# STM_Central_Circuit.net
KiCad netlist of a schematic drawn in EAGLE
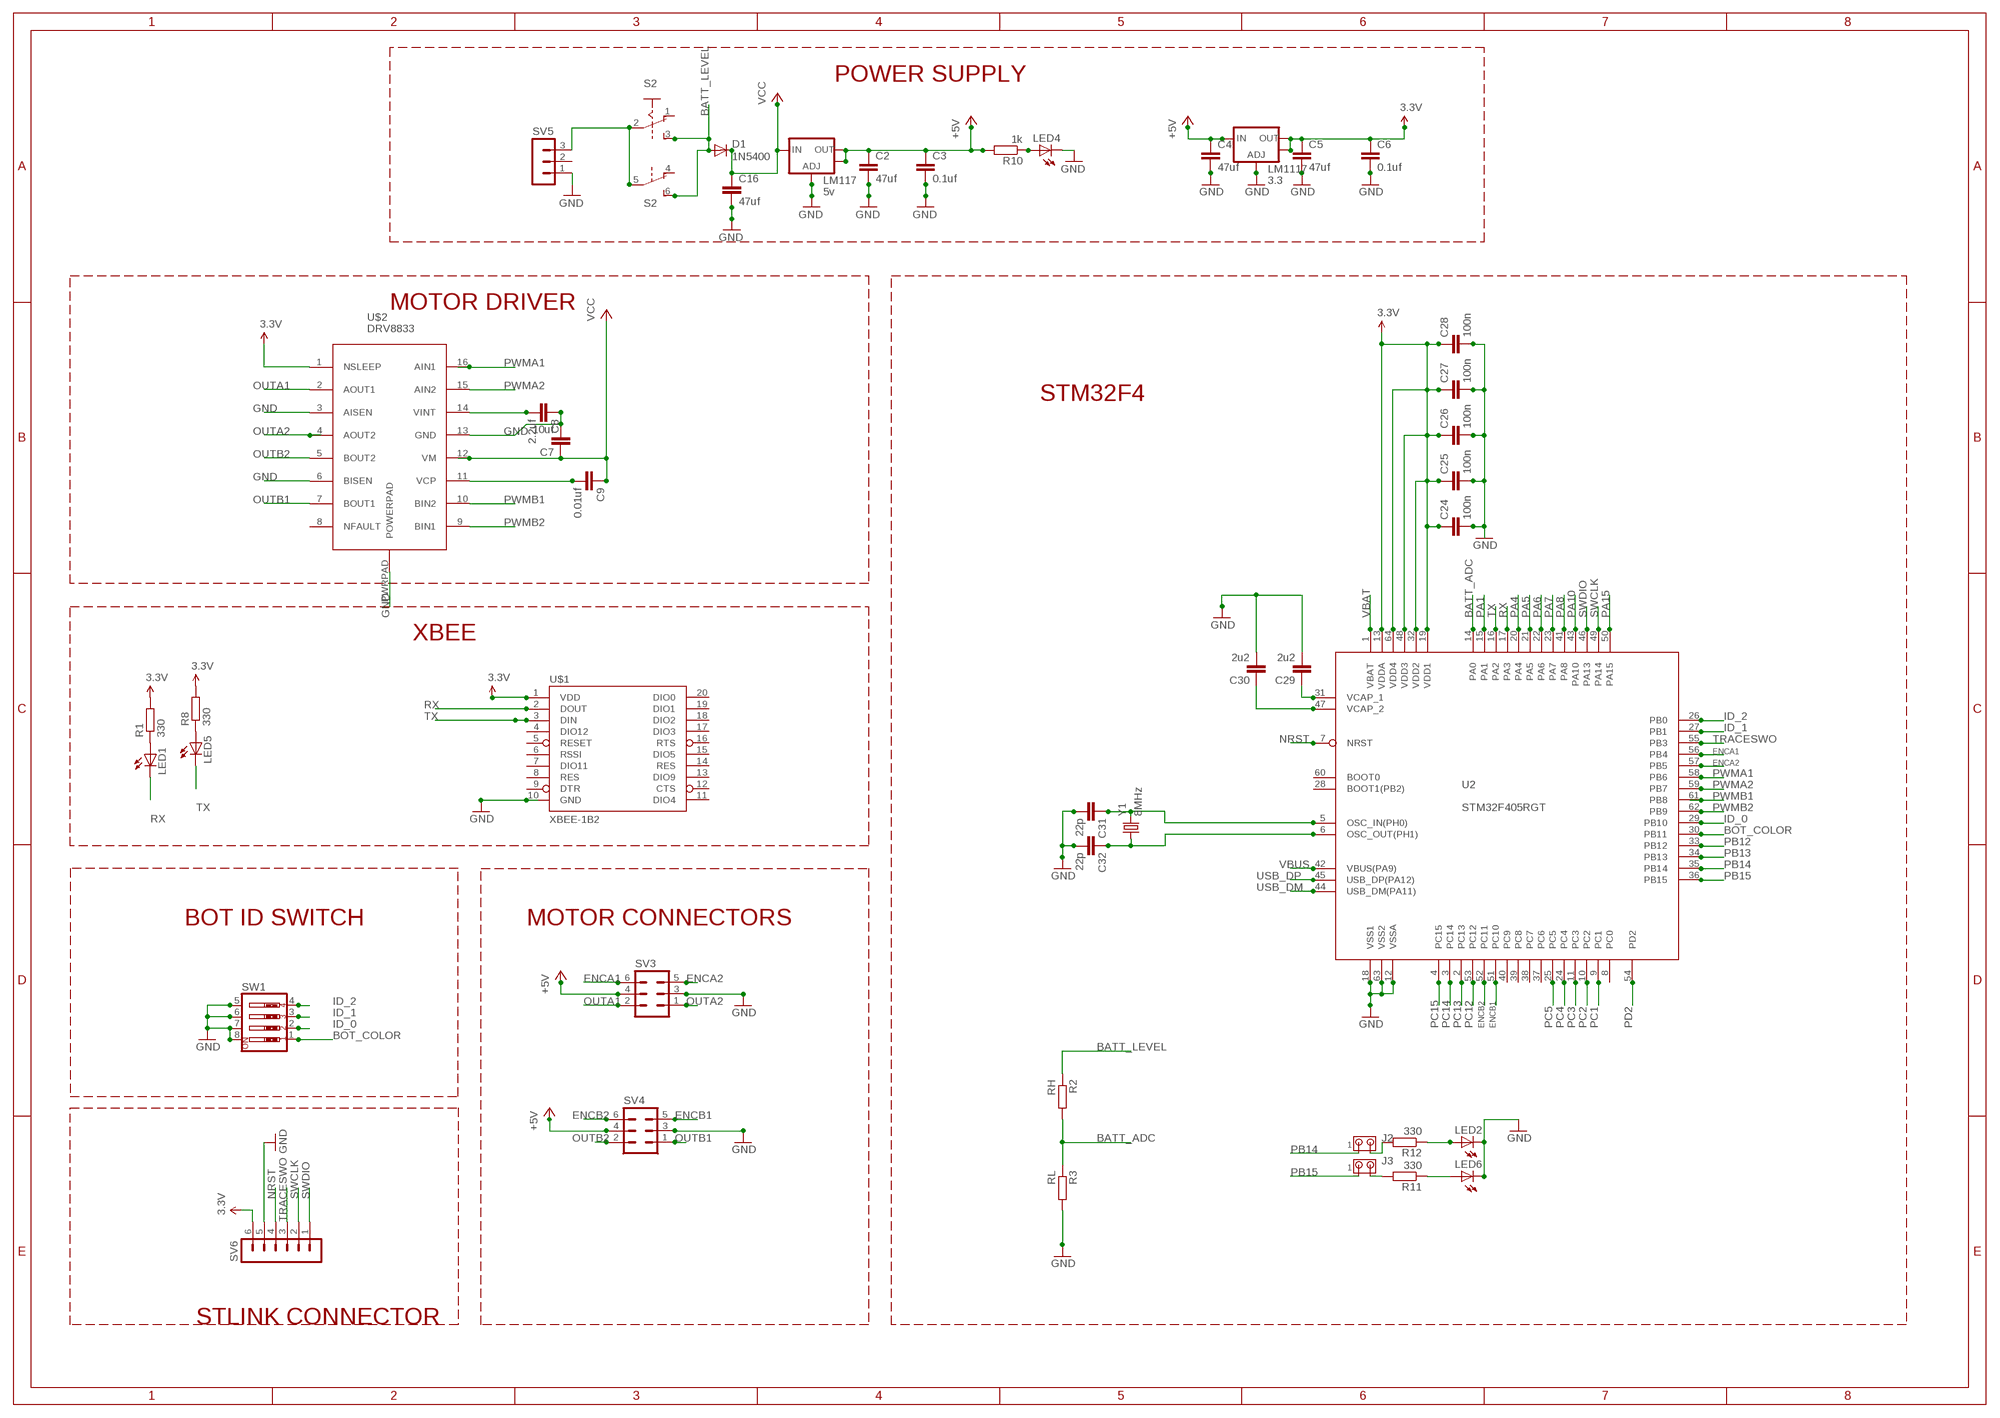
[diagram p0: schematic, sheet 1]

(export (version "E")
  (design (tool "Eeschema 10.0.6"))
  (components
    (comp (ref "C2")
      (value "47uf")
      (footprint "eagle-import:C1206")
      (libsource (lib "eagle-import") (part "C-EUC1206"))
    )
    (comp (ref "C3")
      (value "0.1uf")
      (footprint "eagle-import:C1206")
      (libsource (lib "eagle-import") (part "C-EUC1206"))
    )
    (comp (ref "C4")
      (value "47uf")
      (footprint "eagle-import:C1206")
      (libsource (lib "eagle-import") (part "C-EUC1206"))
    )
    (comp (ref "C5")
      (value "47uf")
      (footprint "eagle-import:C1206")
      (libsource (lib "eagle-import") (part "C-EUC1206"))
    )
    (comp (ref "C6")
      (value "0.1uf")
      (footprint "eagle-import:C1206")
      (libsource (lib "eagle-import") (part "C-EUC1206"))
    )
    (comp (ref "C7")
      (value "10uf")
      (footprint "eagle-import:C1206")
      (libsource (lib "eagle-import") (part "C-EUC1206"))
    )
    (comp (ref "C8")
      (value "2.2uf")
      (footprint "eagle-import:C1206")
      (libsource (lib "eagle-import") (part "C-EUC1206"))
    )
    (comp (ref "C9")
      (value "0.01uf")
      (footprint "eagle-import:C1206")
      (libsource (lib "eagle-import") (part "C-EUC1206"))
    )
    (comp (ref "C16")
      (value "47uf")
      (footprint "eagle-import:C1206")
      (libsource (lib "eagle-import") (part "C-EUC1206"))
    )
    (comp (ref "C24")
      (value "100n")
      (footprint "eagle-import:0603-CAP")
      (libsource (lib "eagle-import") (part "CAP0603-CAP"))
    )
    (comp (ref "C25")
      (value "100n")
      (footprint "eagle-import:0603-CAP")
      (libsource (lib "eagle-import") (part "CAP0603-CAP"))
    )
    (comp (ref "C26")
      (value "100n")
      (footprint "eagle-import:0603-CAP")
      (libsource (lib "eagle-import") (part "CAP0603-CAP"))
    )
    (comp (ref "C27")
      (value "100n")
      (footprint "eagle-import:0603-CAP")
      (libsource (lib "eagle-import") (part "CAP0603-CAP"))
    )
    (comp (ref "C28")
      (value "100n")
      (footprint "eagle-import:0603-CAP")
      (libsource (lib "eagle-import") (part "CAP0603-CAP"))
    )
    (comp (ref "C29")
      (value "2u2")
      (footprint "eagle-import:0603-CAP")
      (libsource (lib "eagle-import") (part "CAP0603-CAP"))
    )
    (comp (ref "C30")
      (value "2u2")
      (footprint "eagle-import:0603-CAP")
      (libsource (lib "eagle-import") (part "CAP0603-CAP"))
    )
    (comp (ref "C31")
      (value "22p")
      (footprint "eagle-import:0603-CAP")
      (libsource (lib "eagle-import") (part "CAP0603-CAP"))
    )
    (comp (ref "C32")
      (value "22p")
      (footprint "eagle-import:0603-CAP")
      (libsource (lib "eagle-import") (part "CAP0603-CAP"))
    )
    (comp (ref "D1")
      (value "1N5400")
      (footprint "eagle-import:DO201-15")
      (libsource (lib "eagle-import") (part "1N5400"))
    )
    (comp (ref "J2")
      (value "MTA02-100")
      (footprint "eagle-import:10X02MTA")
      (libsource (lib "eagle-import") (part "MTA02-100"))
    )
    (comp (ref "J3")
      (value "MTA02-100")
      (footprint "eagle-import:10X02MTA")
      (libsource (lib "eagle-import") (part "MTA02-100"))
    )
    (comp (ref "LED1")
      (value "LED5MM")
      (footprint "eagle-import:LED5MM")
      (libsource (lib "eagle-import") (part "LED5MM"))
    )
    (comp (ref "LED2")
      (value "LED5MM")
      (footprint "eagle-import:LED5MM")
      (libsource (lib "eagle-import") (part "LED5MM"))
    )
    (comp (ref "LED4")
      (value "LED5MM")
      (footprint "eagle-import:LED5MM")
      (libsource (lib "eagle-import") (part "LED5MM"))
    )
    (comp (ref "LED5")
      (value "LED5MM")
      (footprint "eagle-import:LED5MM")
      (libsource (lib "eagle-import") (part "LED5MM"))
    )
    (comp (ref "LED6")
      (value "LED5MM")
      (footprint "eagle-import:LED5MM")
      (libsource (lib "eagle-import") (part "LED5MM"))
    )
    (comp (ref "LM117")
      (value "5v")
      (footprint "eagle-import:SOT223")
      (libsource (lib "eagle-import") (part "V_REG_LM1117SOT223"))
    )
    (comp (ref "LM1117")
      (value "3.3")
      (footprint "eagle-import:SOT223")
      (libsource (lib "eagle-import") (part "V_REG_LM1117SOT223"))
    )
    (comp (ref "R1")
      (value "330")
      (footprint "eagle-import:0207_10")
      (libsource (lib "eagle-import") (part "R-EU_0207/10"))
    )
    (comp (ref "R2")
      (value "RH")
      (footprint "eagle-import:0207_10")
      (libsource (lib "eagle-import") (part "R-EU_0207/10"))
    )
    (comp (ref "R3")
      (value "RL")
      (footprint "eagle-import:0207_10")
      (libsource (lib "eagle-import") (part "R-EU_0207/10"))
    )
    (comp (ref "R8")
      (value "330")
      (footprint "eagle-import:0207_10")
      (libsource (lib "eagle-import") (part "R-EU_0207/10"))
    )
    (comp (ref "R10")
      (value "1k")
      (footprint "eagle-import:0207_10")
      (libsource (lib "eagle-import") (part "R-EU_0207/10"))
    )
    (comp (ref "R11")
      (value "330")
      (footprint "eagle-import:0207_10")
      (libsource (lib "eagle-import") (part "R-EU_0207/10"))
    )
    (comp (ref "R12")
      (value "330")
      (footprint "eagle-import:0207_10")
      (libsource (lib "eagle-import") (part "R-EU_0207/10"))
    )
    (comp (ref "S2")
      (value "A68-A31")
      (footprint "eagle-import:A68-A31")
      (libsource (lib "eagle-import") (part "A68-A31"))
    )
    (comp (ref "SV3")
      (value "MA03-2")
      (footprint "eagle-import:MA03-2")
      (libsource (lib "eagle-import") (part "MA03-2"))
    )
    (comp (ref "SV4")
      (value "MA03-2")
      (footprint "eagle-import:MA03-2")
      (libsource (lib "eagle-import") (part "MA03-2"))
    )
    (comp (ref "SV5")
      (value "MA03-1")
      (footprint "eagle-import:MA03-1")
      (libsource (lib "eagle-import") (part "MA03-1"))
    )
    (comp (ref "SV6")
      (value "MA06-1")
      (footprint "eagle-import:MA06-1")
      (libsource (lib "eagle-import") (part "MA06-1"))
    )
    (comp (ref "SW1")
      (value "SW_DIP-4")
      (footprint "eagle-import:EDG-04")
      (libsource (lib "eagle-import") (part "SW_DIP-4"))
    )
    (comp (ref "U$1")
      (value "XBEE-1B2")
      (footprint "eagle-import:XBEE-SILK")
      (libsource (lib "eagle-import") (part "XBEE-1B2"))
    )
    (comp (ref "U$2")
      (value "DRV8833")
      (footprint "eagle-import:PWP_R_PDSO_G16")
      (libsource (lib "eagle-import") (part "DRV8833"))
    )
    (comp (ref "U2")
      (value "STM32F405RGT")
      (footprint "eagle-import:LQFP64")
      (libsource (lib "eagle-import") (part "STM32F405RGT"))
    )
    (comp (ref "Y1")
      (value "8MHz")
      (footprint "eagle-import:CRYSTAL-SMD-5X3")
      (libsource (lib "eagle-import") (part "CRYSTAL5X3"))
    )
  )
  (nets
    (net (code "1") (name "+5V") (class "Default")
      (node (ref "C2") (pin "1") (pinfunction "1_1") (pintype "passive"))
      (node (ref "C3") (pin "1") (pinfunction "1_1") (pintype "passive"))
      (node (ref "C4") (pin "1") (pinfunction "1_1") (pintype "passive"))
      (node (ref "LM1117") (pin "3") (pinfunction "IN_3") (pintype "input"))
      (node (ref "LM117") (pin "2") (pinfunction "OUT_2") (pintype "output"))
      (node (ref "LM117") (pin "4") (pinfunction "OUT_4") (pintype "output"))
      (node (ref "R10") (pin "2") (pinfunction "2_2") (pintype "passive"))
      (node (ref "SV3") (pin "4") (pinfunction "4_4") (pintype "passive"))
      (node (ref "SV4") (pin "4") (pinfunction "4_4") (pintype "passive"))
    )
    (net (code "2") (name "/BATT_ADC") (class "Default")
      (node (ref "R2") (pin "2") (pinfunction "2_2") (pintype "passive"))
      (node (ref "R3") (pin "1") (pinfunction "1_1") (pintype "passive"))
      (node (ref "U2") (pin "14") (pinfunction "PA0_14") (pintype "bidirectional"))
    )
    (net (code "3") (name "/BATT_LEVEL") (class "Default")
      (node (ref "D1") (pin "A") (pinfunction "A_A") (pintype "passive"))
      (node (ref "R2") (pin "1") (pinfunction "1_1") (pintype "passive"))
      (node (ref "S2") (pin "3") (pinfunction "S_3") (pintype "passive"))
      (node (ref "S2") (pin "6") (pinfunction "S_6") (pintype "passive"))
    )
    (net (code "4") (name "/BOT_COLOR") (class "Default")
      (node (ref "SW1") (pin "1") (pinfunction "1_1") (pintype "passive"))
      (node (ref "U2") (pin "30") (pinfunction "PB11_30") (pintype "bidirectional"))
    )
    (net (code "5") (name "/ENCA1") (class "Default")
      (node (ref "SV3") (pin "6") (pinfunction "6_6") (pintype "passive"))
      (node (ref "U2") (pin "56") (pinfunction "PB4_56") (pintype "bidirectional"))
    )
    (net (code "6") (name "/ENCA2") (class "Default")
      (node (ref "SV3") (pin "5") (pinfunction "5_5") (pintype "passive"))
      (node (ref "U2") (pin "57") (pinfunction "PB5_57") (pintype "bidirectional"))
    )
    (net (code "7") (name "/ENCB1") (class "Default")
      (node (ref "SV4") (pin "5") (pinfunction "5_5") (pintype "passive"))
      (node (ref "U2") (pin "51") (pinfunction "PC10_51") (pintype "bidirectional"))
    )
    (net (code "8") (name "/ENCB2") (class "Default")
      (node (ref "SV4") (pin "6") (pinfunction "6_6") (pintype "passive"))
      (node (ref "U2") (pin "52") (pinfunction "PC11_52") (pintype "bidirectional"))
    )
    (net (code "9") (name "/ID_0") (class "Default")
      (node (ref "SW1") (pin "2") (pinfunction "2_2") (pintype "passive"))
      (node (ref "U2") (pin "29") (pinfunction "PB10_29") (pintype "bidirectional"))
    )
    (net (code "10") (name "/ID_1") (class "Default")
      (node (ref "SW1") (pin "3") (pinfunction "3_3") (pintype "passive"))
      (node (ref "U2") (pin "27") (pinfunction "PB1_27") (pintype "bidirectional"))
    )
    (net (code "11") (name "/ID_2") (class "Default")
      (node (ref "SW1") (pin "4") (pinfunction "4_4") (pintype "passive"))
      (node (ref "U2") (pin "26") (pinfunction "PB0_26") (pintype "bidirectional"))
    )
    (net (code "12") (name "/NRST") (class "Default")
      (node (ref "SV6") (pin "4") (pinfunction "4_4") (pintype "passive"))
      (node (ref "U2") (pin "7") (pinfunction "NRST_7") (pintype "input"))
    )
    (net (code "13") (name "/OUTA1") (class "Default")
      (node (ref "SV3") (pin "2") (pinfunction "2_2") (pintype "passive"))
      (node (ref "U$2") (pin "2") (pinfunction "AOUT1_2") (pintype "bidirectional"))
    )
    (net (code "14") (name "/OUTA2") (class "Default")
      (node (ref "SV3") (pin "1") (pinfunction "1_1") (pintype "passive"))
      (node (ref "U$2") (pin "4") (pinfunction "AOUT2_4") (pintype "bidirectional"))
    )
    (net (code "15") (name "/OUTB1") (class "Default")
      (node (ref "SV4") (pin "1") (pinfunction "1_1") (pintype "passive"))
      (node (ref "U$2") (pin "7") (pinfunction "BOUT1_7") (pintype "bidirectional"))
    )
    (net (code "16") (name "/OUTB2") (class "Default")
      (node (ref "SV4") (pin "2") (pinfunction "2_2") (pintype "passive"))
      (node (ref "U$2") (pin "5") (pinfunction "BOUT2_5") (pintype "bidirectional"))
    )
    (net (code "17") (name "/PA1") (class "Default")
      (node (ref "U2") (pin "15") (pinfunction "PA1_15") (pintype "bidirectional"))
    )
    (net (code "18") (name "/PA4") (class "Default")
      (node (ref "U2") (pin "20") (pinfunction "PA4_20") (pintype "bidirectional"))
    )
    (net (code "19") (name "/PA5") (class "Default")
      (node (ref "U2") (pin "21") (pinfunction "PA5_21") (pintype "bidirectional"))
    )
    (net (code "20") (name "/PA6") (class "Default")
      (node (ref "U2") (pin "22") (pinfunction "PA6_22") (pintype "bidirectional"))
    )
    (net (code "21") (name "/PA7") (class "Default")
      (node (ref "U2") (pin "23") (pinfunction "PA7_23") (pintype "bidirectional"))
    )
    (net (code "22") (name "/PA8") (class "Default")
      (node (ref "U2") (pin "41") (pinfunction "PA8_41") (pintype "bidirectional"))
    )
    (net (code "23") (name "/PA10") (class "Default")
      (node (ref "U2") (pin "43") (pinfunction "PA10_43") (pintype "bidirectional"))
    )
    (net (code "24") (name "/PA15") (class "Default")
      (node (ref "U2") (pin "50") (pinfunction "PA15_50") (pintype "bidirectional"))
    )
    (net (code "25") (name "/PB12") (class "Default")
      (node (ref "U2") (pin "33") (pinfunction "PB12_33") (pintype "bidirectional"))
    )
    (net (code "26") (name "/PB13") (class "Default")
      (node (ref "U2") (pin "34") (pinfunction "PB13_34") (pintype "bidirectional"))
    )
    (net (code "27") (name "/PB14") (class "Default")
      (node (ref "J2") (pin "1") (pinfunction "1_1") (pintype "passive"))
      (node (ref "U2") (pin "35") (pinfunction "PB14_35") (pintype "bidirectional"))
    )
    (net (code "28") (name "/PB15") (class "Default")
      (node (ref "J3") (pin "1") (pinfunction "1_1") (pintype "passive"))
      (node (ref "U2") (pin "36") (pinfunction "PB15_36") (pintype "bidirectional"))
    )
    (net (code "29") (name "/PC1") (class "Default")
      (node (ref "U2") (pin "9") (pinfunction "PC1_9") (pintype "bidirectional"))
    )
    (net (code "30") (name "/PC2") (class "Default")
      (node (ref "U2") (pin "10") (pinfunction "PC2_10") (pintype "bidirectional"))
    )
    (net (code "31") (name "/PC3") (class "Default")
      (node (ref "U2") (pin "11") (pinfunction "PC3_11") (pintype "bidirectional"))
    )
    (net (code "32") (name "/PC4") (class "Default")
      (node (ref "U2") (pin "24") (pinfunction "PC4_24") (pintype "bidirectional"))
    )
    (net (code "33") (name "/PC5") (class "Default")
      (node (ref "U2") (pin "25") (pinfunction "PC5_25") (pintype "bidirectional"))
    )
    (net (code "34") (name "/PC12") (class "Default")
      (node (ref "U2") (pin "53") (pinfunction "PC12_53") (pintype "bidirectional"))
    )
    (net (code "35") (name "/PC13") (class "Default")
      (node (ref "U2") (pin "2") (pinfunction "PC13_2") (pintype "bidirectional"))
    )
    (net (code "36") (name "/PC14") (class "Default")
      (node (ref "U2") (pin "3") (pinfunction "PC14_3") (pintype "bidirectional"))
    )
    (net (code "37") (name "/PC15") (class "Default")
      (node (ref "U2") (pin "4") (pinfunction "PC15_4") (pintype "bidirectional"))
    )
    (net (code "38") (name "/PD2") (class "Default")
      (node (ref "U2") (pin "54") (pinfunction "PD2_54") (pintype "bidirectional"))
    )
    (net (code "39") (name "/PWMA1") (class "Default")
      (node (ref "U$2") (pin "16") (pinfunction "AIN1_16") (pintype "bidirectional"))
      (node (ref "U2") (pin "58") (pinfunction "PB6_58") (pintype "bidirectional"))
    )
    (net (code "40") (name "/PWMA2") (class "Default")
      (node (ref "U$2") (pin "15") (pinfunction "AIN2_15") (pintype "bidirectional"))
      (node (ref "U2") (pin "59") (pinfunction "PB7_59") (pintype "bidirectional"))
    )
    (net (code "41") (name "/PWMB1") (class "Default")
      (node (ref "U$2") (pin "10") (pinfunction "BIN2_10") (pintype "bidirectional"))
      (node (ref "U2") (pin "61") (pinfunction "PB8_61") (pintype "bidirectional"))
    )
    (net (code "42") (name "/PWMB2") (class "Default")
      (node (ref "U$2") (pin "9") (pinfunction "BIN1_9") (pintype "bidirectional"))
      (node (ref "U2") (pin "62") (pinfunction "PB9_62") (pintype "bidirectional"))
    )
    (net (code "43") (name "/RX") (class "Default")
      (node (ref "LED1") (pin "K") (pinfunction "C_K") (pintype "passive"))
      (node (ref "U$1") (pin "2") (pinfunction "DOUT_2") (pintype "output"))
      (node (ref "U2") (pin "17") (pinfunction "PA3_17") (pintype "bidirectional"))
    )
    (net (code "44") (name "/SWCLK") (class "Default")
      (node (ref "SV6") (pin "2") (pinfunction "2_2") (pintype "passive"))
      (node (ref "U2") (pin "49") (pinfunction "PA14_49") (pintype "bidirectional"))
    )
    (net (code "45") (name "/SWDIO") (class "Default")
      (node (ref "SV6") (pin "1") (pinfunction "1_1") (pintype "passive"))
      (node (ref "U2") (pin "46") (pinfunction "PA13_46") (pintype "bidirectional"))
    )
    (net (code "46") (name "/TRACESWO") (class "Default")
      (node (ref "SV6") (pin "3") (pinfunction "3_3") (pintype "passive"))
      (node (ref "U2") (pin "55") (pinfunction "PB3_55") (pintype "bidirectional"))
    )
    (net (code "47") (name "/TX") (class "Default")
      (node (ref "LED5") (pin "K") (pinfunction "C_K") (pintype "passive"))
      (node (ref "U$1") (pin "3") (pinfunction "DIN_3") (pintype "input"))
      (node (ref "U2") (pin "16") (pinfunction "PA2_16") (pintype "bidirectional"))
    )
    (net (code "48") (name "/USB_DM") (class "Default")
      (node (ref "U2") (pin "44") (pinfunction "USB_DM(PA11)_44") (pintype "bidirectional"))
    )
    (net (code "49") (name "/USB_DP") (class "Default")
      (node (ref "U2") (pin "45") (pinfunction "USB_DP(PA12)_45") (pintype "bidirectional"))
    )
    (net (code "50") (name "/VBAT") (class "Default")
      (node (ref "U2") (pin "1") (pinfunction "VBAT_1") (pintype "power_in"))
    )
    (net (code "51") (name "/VBUS") (class "Default")
      (node (ref "U2") (pin "42") (pinfunction "VBUS(PA9)_42") (pintype "bidirectional"))
    )
    (net (code "52") (name "3.3V") (class "Default")
      (node (ref "C24") (pin "1") (pinfunction "1_1") (pintype "passive"))
      (node (ref "C25") (pin "1") (pinfunction "1_1") (pintype "passive"))
      (node (ref "C26") (pin "1") (pinfunction "1_1") (pintype "passive"))
      (node (ref "C27") (pin "1") (pinfunction "1_1") (pintype "passive"))
      (node (ref "C28") (pin "1") (pinfunction "1_1") (pintype "passive"))
      (node (ref "C5") (pin "1") (pinfunction "1_1") (pintype "passive"))
      (node (ref "C6") (pin "1") (pinfunction "1_1") (pintype "passive"))
      (node (ref "LM1117") (pin "2") (pinfunction "OUT_2") (pintype "output"))
      (node (ref "LM1117") (pin "4") (pinfunction "OUT_4") (pintype "output"))
      (node (ref "R1") (pin "2") (pinfunction "2_2") (pintype "passive"))
      (node (ref "R8") (pin "2") (pinfunction "2_2") (pintype "passive"))
      (node (ref "SV6") (pin "6") (pinfunction "6_6") (pintype "passive"))
      (node (ref "U$1") (pin "1") (pinfunction "VDD_1") (pintype "power_in"))
      (node (ref "U$2") (pin "1") (pinfunction "NSLEEP_1") (pintype "bidirectional"))
      (node (ref "U2") (pin "13") (pinfunction "VDDA_13") (pintype "power_in"))
      (node (ref "U2") (pin "19") (pinfunction "VDD1_19") (pintype "power_in"))
      (node (ref "U2") (pin "32") (pinfunction "VDD2_32") (pintype "power_in"))
      (node (ref "U2") (pin "48") (pinfunction "VDD3_48") (pintype "power_in"))
      (node (ref "U2") (pin "64") (pinfunction "VDD4_64") (pintype "power_in"))
    )
    (net (code "53") (name "GND") (class "Default")
      (node (ref "C16") (pin "2") (pinfunction "2_2") (pintype "passive"))
      (node (ref "C2") (pin "2") (pinfunction "2_2") (pintype "passive"))
      (node (ref "C24") (pin "2") (pinfunction "2_2") (pintype "passive"))
      (node (ref "C25") (pin "2") (pinfunction "2_2") (pintype "passive"))
      (node (ref "C26") (pin "2") (pinfunction "2_2") (pintype "passive"))
      (node (ref "C27") (pin "2") (pinfunction "2_2") (pintype "passive"))
      (node (ref "C28") (pin "2") (pinfunction "2_2") (pintype "passive"))
      (node (ref "C29") (pin "2") (pinfunction "2_2") (pintype "passive"))
      (node (ref "C3") (pin "2") (pinfunction "2_2") (pintype "passive"))
      (node (ref "C30") (pin "2") (pinfunction "2_2") (pintype "passive"))
      (node (ref "C31") (pin "2") (pinfunction "2_2") (pintype "passive"))
      (node (ref "C32") (pin "2") (pinfunction "2_2") (pintype "passive"))
      (node (ref "C4") (pin "2") (pinfunction "2_2") (pintype "passive"))
      (node (ref "C5") (pin "2") (pinfunction "2_2") (pintype "passive"))
      (node (ref "C6") (pin "2") (pinfunction "2_2") (pintype "passive"))
      (node (ref "C7") (pin "2") (pinfunction "2_2") (pintype "passive"))
      (node (ref "C8") (pin "1") (pinfunction "1_1") (pintype "passive"))
      (node (ref "LED2") (pin "K") (pinfunction "C_K") (pintype "passive"))
      (node (ref "LED4") (pin "K") (pinfunction "C_K") (pintype "passive"))
      (node (ref "LED6") (pin "K") (pinfunction "C_K") (pintype "passive"))
      (node (ref "LM1117") (pin "1") (pinfunction "ADJ_1") (pintype "input"))
      (node (ref "LM117") (pin "1") (pinfunction "ADJ_1") (pintype "input"))
      (node (ref "R3") (pin "2") (pinfunction "2_2") (pintype "passive"))
      (node (ref "SV3") (pin "3") (pinfunction "3_3") (pintype "passive"))
      (node (ref "SV4") (pin "3") (pinfunction "3_3") (pintype "passive"))
      (node (ref "SV5") (pin "1") (pinfunction "1_1") (pintype "passive"))
      (node (ref "SV6") (pin "5") (pinfunction "5_5") (pintype "passive"))
      (node (ref "SW1") (pin "5") (pinfunction "5_5") (pintype "passive"))
      (node (ref "SW1") (pin "6") (pinfunction "6_6") (pintype "passive"))
      (node (ref "SW1") (pin "7") (pinfunction "7_7") (pintype "passive"))
      (node (ref "SW1") (pin "8") (pinfunction "8_8") (pintype "passive"))
      (node (ref "U$1") (pin "10") (pinfunction "GND_10") (pintype "power_in"))
      (node (ref "U$2") (pin "13") (pinfunction "GND_13") (pintype "bidirectional"))
      (node (ref "U$2") (pin "3") (pinfunction "AISEN_3") (pintype "bidirectional"))
      (node (ref "U$2") (pin "6") (pinfunction "BISEN_6") (pintype "bidirectional"))
      (node (ref "U$2") (pin "PWRPAD") (pinfunction "POWERPAD_PWRPAD") (pintype "bidirectional"))
      (node (ref "U2") (pin "12") (pinfunction "VSSA_12") (pintype "power_in"))
      (node (ref "U2") (pin "18") (pinfunction "VSS1_18") (pintype "power_in"))
      (node (ref "U2") (pin "63") (pinfunction "VSS2_63") (pintype "power_in"))
    )
    (net (code "54") (name "Net-(J2-Pad2)") (class "Default")
      (node (ref "J2") (pin "2") (pinfunction "2_2") (pintype "passive"))
      (node (ref "R12") (pin "2") (pinfunction "2_2") (pintype "passive"))
    )
    (net (code "55") (name "Net-(J3-Pad2)") (class "Default")
      (node (ref "J3") (pin "2") (pinfunction "2_2") (pintype "passive"))
      (node (ref "R11") (pin "2") (pinfunction "2_2") (pintype "passive"))
    )
    (net (code "56") (name "Net-(LED1-PadA)") (class "Default")
      (node (ref "LED1") (pin "A") (pinfunction "A_A") (pintype "passive"))
      (node (ref "R1") (pin "1") (pinfunction "1_1") (pintype "passive"))
    )
    (net (code "57") (name "Net-(LED2-PadA)") (class "Default")
      (node (ref "LED2") (pin "A") (pinfunction "A_A") (pintype "passive"))
      (node (ref "R12") (pin "1") (pinfunction "1_1") (pintype "passive"))
    )
    (net (code "58") (name "Net-(LED4-PadA)") (class "Default")
      (node (ref "LED4") (pin "A") (pinfunction "A_A") (pintype "passive"))
      (node (ref "R10") (pin "1") (pinfunction "1_1") (pintype "passive"))
    )
    (net (code "59") (name "Net-(LED5-PadA)") (class "Default")
      (node (ref "LED5") (pin "A") (pinfunction "A_A") (pintype "passive"))
      (node (ref "R8") (pin "1") (pinfunction "1_1") (pintype "passive"))
    )
    (net (code "60") (name "Net-(LED6-PadA)") (class "Default")
      (node (ref "LED6") (pin "A") (pinfunction "A_A") (pintype "passive"))
      (node (ref "R11") (pin "1") (pinfunction "1_1") (pintype "passive"))
    )
    (net (code "61") (name "Net-(S2A-P)") (class "Default")
      (node (ref "S2") (pin "2") (pinfunction "P_2") (pintype "passive"))
      (node (ref "S2") (pin "5") (pinfunction "P_5") (pintype "passive"))
      (node (ref "SV5") (pin "3") (pinfunction "3_3") (pintype "passive"))
    )
    (net (code "62") (name "Net-(U$2-VCP)") (class "Default")
      (node (ref "C9") (pin "2") (pinfunction "2_2") (pintype "passive"))
      (node (ref "U$2") (pin "11") (pinfunction "VCP_11") (pintype "bidirectional"))
    )
    (net (code "63") (name "Net-(U$2-VINT)") (class "Default")
      (node (ref "C8") (pin "2") (pinfunction "2_2") (pintype "passive"))
      (node (ref "U$2") (pin "14") (pinfunction "VINT_14") (pintype "bidirectional"))
    )
    (net (code "64") (name "Net-(U2-OSC_IN(PH0))") (class "Default")
      (node (ref "C31") (pin "1") (pinfunction "1_1") (pintype "passive"))
      (node (ref "U2") (pin "5") (pinfunction "OSC_IN(PH0)_5") (pintype "bidirectional"))
      (node (ref "Y1") (pin "3") (pinfunction "2_3") (pintype "passive"))
    )
    (net (code "65") (name "Net-(U2-OSC_OUT(PH1))") (class "Default")
      (node (ref "C32") (pin "1") (pinfunction "1_1") (pintype "passive"))
      (node (ref "U2") (pin "6") (pinfunction "OSC_OUT(PH1)_6") (pintype "bidirectional"))
      (node (ref "Y1") (pin "1") (pinfunction "1_1") (pintype "passive"))
    )
    (net (code "66") (name "Net-(U2-VCAP_1)") (class "Default")
      (node (ref "C29") (pin "1") (pinfunction "1_1") (pintype "passive"))
      (node (ref "U2") (pin "31") (pinfunction "VCAP_1_31") (pintype "bidirectional"))
    )
    (net (code "67") (name "Net-(U2-VCAP_2)") (class "Default")
      (node (ref "C30") (pin "1") (pinfunction "1_1") (pintype "passive"))
      (node (ref "U2") (pin "47") (pinfunction "VCAP_2_47") (pintype "bidirectional"))
    )
    (net (code "68") (name "VCC") (class "Default")
      (node (ref "C16") (pin "1") (pinfunction "1_1") (pintype "passive"))
      (node (ref "C7") (pin "1") (pinfunction "1_1") (pintype "passive"))
      (node (ref "C9") (pin "1") (pinfunction "1_1") (pintype "passive"))
      (node (ref "D1") (pin "C") (pinfunction "C_C") (pintype "passive"))
      (node (ref "LM117") (pin "3") (pinfunction "IN_3") (pintype "input"))
      (node (ref "U$2") (pin "12") (pinfunction "VM_12") (pintype "bidirectional"))
    )
    (net (code "69") (name "unconnected-(S2A-O-Pad1)") (class "Default")
      (node (ref "S2") (pin "1") (pinfunction "O_1") (pintype "passive"))
    )
    (net (code "70") (name "unconnected-(S2B-O-Pad4)") (class "Default")
      (node (ref "S2") (pin "4") (pinfunction "O_4") (pintype "passive"))
    )
    (net (code "71") (name "unconnected-(SV5-Pad2)") (class "Default")
      (node (ref "SV5") (pin "2") (pinfunction "2_2") (pintype "passive"))
    )
    (net (code "72") (name "unconnected-(U$1-CTS-Pad12)") (class "Default")
      (node (ref "U$1") (pin "12") (pinfunction "CTS_12") (pintype "output"))
    )
    (net (code "73") (name "unconnected-(U$1-DIO0-Pad20)") (class "Default")
      (node (ref "U$1") (pin "20") (pinfunction "DIO0_20") (pintype "bidirectional"))
    )
    (net (code "74") (name "unconnected-(U$1-DIO1-Pad19)") (class "Default")
      (node (ref "U$1") (pin "19") (pinfunction "DIO1_19") (pintype "bidirectional"))
    )
    (net (code "75") (name "unconnected-(U$1-DIO2-Pad18)") (class "Default")
      (node (ref "U$1") (pin "18") (pinfunction "DIO2_18") (pintype "bidirectional"))
    )
    (net (code "76") (name "unconnected-(U$1-DIO3-Pad17)") (class "Default")
      (node (ref "U$1") (pin "17") (pinfunction "DIO3_17") (pintype "bidirectional"))
    )
    (net (code "77") (name "unconnected-(U$1-DIO4-Pad11)") (class "Default")
      (node (ref "U$1") (pin "11") (pinfunction "DIO4_11") (pintype "bidirectional"))
    )
    (net (code "78") (name "unconnected-(U$1-DIO5-Pad15)") (class "Default")
      (node (ref "U$1") (pin "15") (pinfunction "DIO5_15") (pintype "bidirectional"))
    )
    (net (code "79") (name "unconnected-(U$1-DIO9-Pad13)") (class "Default")
      (node (ref "U$1") (pin "13") (pinfunction "DIO9_13") (pintype "bidirectional"))
    )
    (net (code "80") (name "unconnected-(U$1-DIO11-Pad7)") (class "Default")
      (node (ref "U$1") (pin "7") (pinfunction "DIO11_7") (pintype "bidirectional"))
    )
    (net (code "81") (name "unconnected-(U$1-DIO12-Pad4)") (class "Default")
      (node (ref "U$1") (pin "4") (pinfunction "DIO12_4") (pintype "bidirectional"))
    )
    (net (code "82") (name "unconnected-(U$1-DTR-Pad9)") (class "Default")
      (node (ref "U$1") (pin "9") (pinfunction "DTR_9") (pintype "bidirectional"))
    )
    (net (code "83") (name "unconnected-(U$1-RES-Pad8)") (class "Default")
      (node (ref "U$1") (pin "8") (pinfunction "RES_8") (pintype "bidirectional"))
    )
    (net (code "84") (name "unconnected-(U$1-RES-Pad14)") (class "Default")
      (node (ref "U$1") (pin "14") (pinfunction "RES_14") (pintype "bidirectional"))
    )
    (net (code "85") (name "unconnected-(U$1-RESET-Pad5)") (class "Default")
      (node (ref "U$1") (pin "5") (pinfunction "RESET_5") (pintype "input"))
    )
    (net (code "86") (name "unconnected-(U$1-RSSI-Pad6)") (class "Default")
      (node (ref "U$1") (pin "6") (pinfunction "RSSI_6") (pintype "bidirectional"))
    )
    (net (code "87") (name "unconnected-(U$1-RTS-Pad16)") (class "Default")
      (node (ref "U$1") (pin "16") (pinfunction "RTS_16") (pintype "input"))
    )
    (net (code "88") (name "unconnected-(U$2-NFAULT-Pad8)") (class "Default")
      (node (ref "U$2") (pin "8") (pinfunction "NFAULT_8") (pintype "bidirectional"))
    )
    (net (code "89") (name "unconnected-(U2-BOOT0-Pad60)") (class "Default")
      (node (ref "U2") (pin "60") (pinfunction "BOOT0_60") (pintype "input"))
    )
    (net (code "90") (name "unconnected-(U2-BOOT1(PB2)-Pad28)") (class "Default")
      (node (ref "U2") (pin "28") (pinfunction "BOOT1(PB2)_28") (pintype "input"))
    )
    (net (code "91") (name "unconnected-(U2-PC0-Pad8)") (class "Default")
      (node (ref "U2") (pin "8") (pinfunction "PC0_8") (pintype "bidirectional"))
    )
    (net (code "92") (name "unconnected-(U2-PC6-Pad37)") (class "Default")
      (node (ref "U2") (pin "37") (pinfunction "PC6_37") (pintype "bidirectional"))
    )
    (net (code "93") (name "unconnected-(U2-PC7-Pad38)") (class "Default")
      (node (ref "U2") (pin "38") (pinfunction "PC7_38") (pintype "bidirectional"))
    )
    (net (code "94") (name "unconnected-(U2-PC8-Pad39)") (class "Default")
      (node (ref "U2") (pin "39") (pinfunction "PC8_39") (pintype "bidirectional"))
    )
    (net (code "95") (name "unconnected-(U2-PC9-Pad40)") (class "Default")
      (node (ref "U2") (pin "40") (pinfunction "PC9_40") (pintype "bidirectional"))
    )
  )
)
